# TOP.net
KiCad netlist of a schematic drawn in Altium Designer
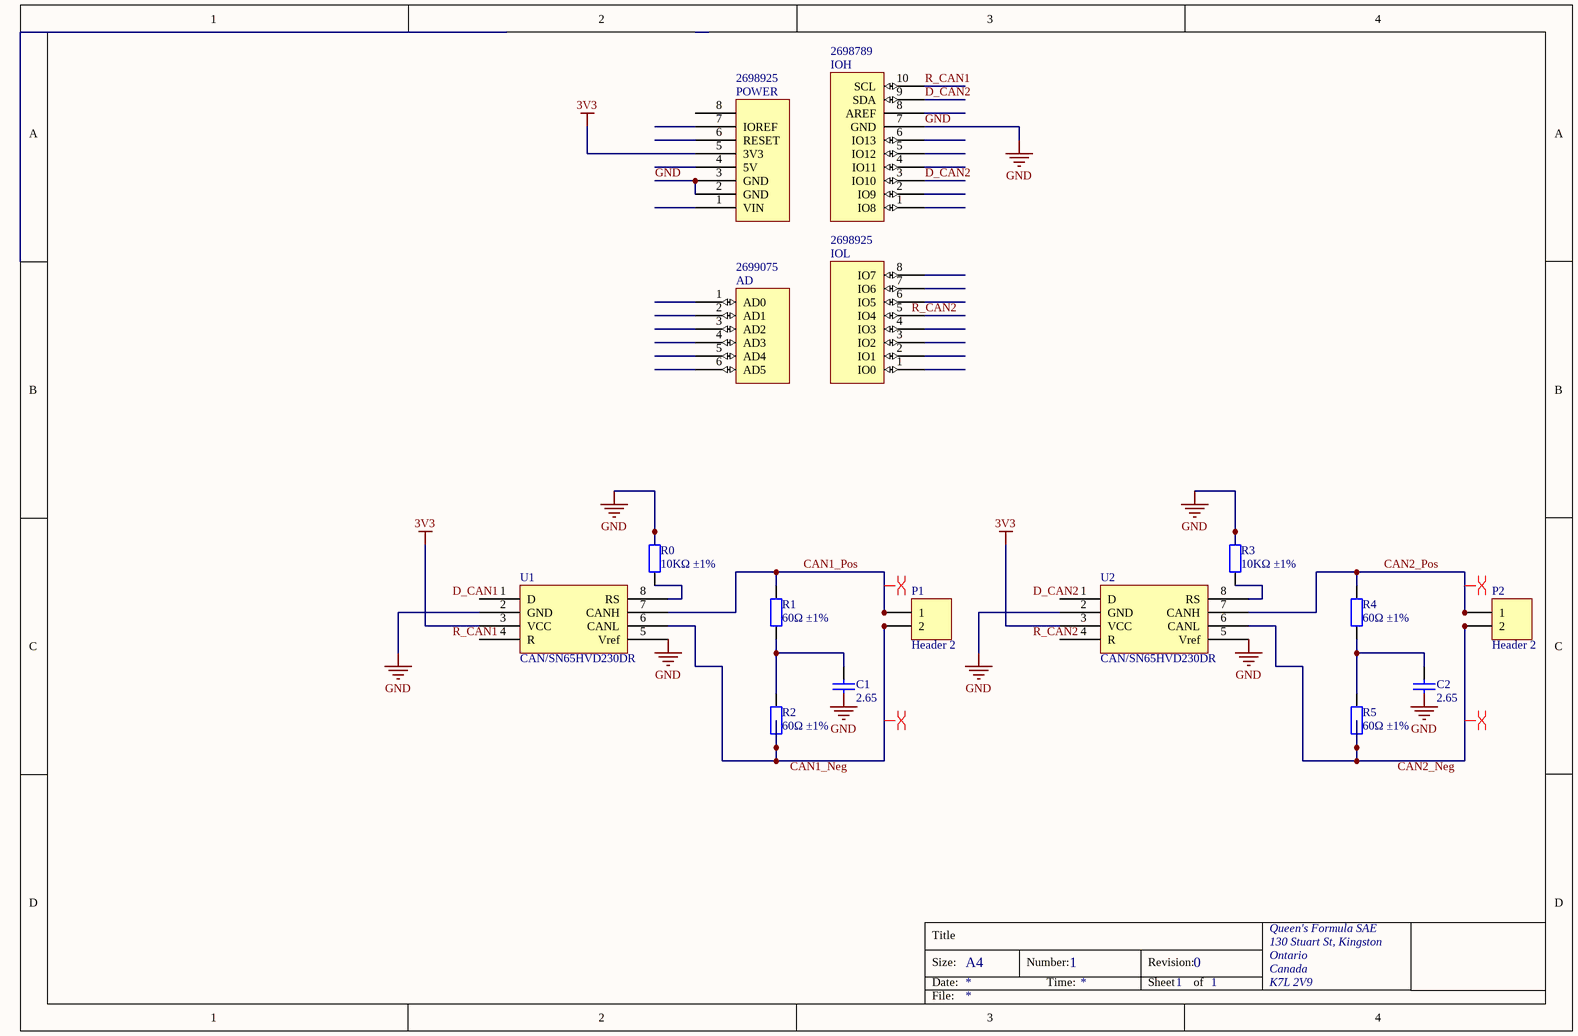
[diagram p0: TOP.SchDoc]

(export (version "E")
  (design (tool "Eeschema 10.0.6"))
  (components
    (comp (ref "AD")
      (value "AD")
      (footprint "Header:Header 6x1 8.5mm")
      (fields (field (name "SUPPLIER PART NUMBER 4") "2699075"))
      (libsource (lib "Header") (part "AD"))
    )
    (comp (ref "C1")
      (value "2.65")
      (footprint "0402_C")
      (description "Chip capacitor")
      (fields
        (field (name "MANUFACTURER") "Guangdong Fenghua Advanced Tech")
        (field (name "PARTNUMBER") "0402B102K500NT")
      )
      (libsource (lib "Cap") (part "0402 1nF (102) 10% 50V"))
    )
    (comp (ref "C2")
      (value "2.65")
      (footprint "0402_C")
      (description "Chip capacitor")
      (fields
        (field (name "MANUFACTURER") "Guangdong Fenghua Advanced Tech")
        (field (name "PARTNUMBER") "0402B102K500NT")
      )
      (libsource (lib "Cap") (part "0402 1nF (102) 10% 50V"))
    )
    (comp (ref "IOH")
      (value "IOH")
      (footprint "Header:Header 10x1 8.5mm")
      (fields (field (name "SUPPLIER PART NUMBER 3") "2698789"))
      (libsource (lib "Header") (part "IOH"))
    )
    (comp (ref "IOL")
      (value "IOL")
      (footprint "Header 8x1 8.5mm")
      (fields (field (name "SUPPLIER PART NUMBER 4") "2698925"))
      (libsource (lib "Header") (part "IOL"))
    )
    (comp (ref "P1")
      (value "Header 2")
      (footprint "HDR1X2")
      (description "Header, 2-Pin")
      (fields (field (name "PUBLISHER") "Altium Limited"))
      (libsource (lib "Miscellaneous Connectors") (part "Header 2"))
    )
    (comp (ref "P2")
      (value "Header 2")
      (footprint "HDR1X2")
      (description "Header, 2-Pin")
      (fields (field (name "PUBLISHER") "Altium Limited"))
      (libsource (lib "Miscellaneous Connectors") (part "Header 2"))
    )
    (comp (ref "POWER")
      (value "POWER_UNO")
      (footprint "Header 8x1 8.5mm")
      (fields (field (name "SUPPLIER PART NUMBER 4") "2698925"))
      (libsource (lib "Header") (part "POWER_UNO"))
    )
    (comp (ref "R0")
      (value "10KΩ ±1%")
      (footprint "0402_R")
      (description "Chip resistor")
      (fields (field (name "MANUFACTURER") "Uniroyal Elec") (field (name "PARTNUMBER") "0402WGF1002TCE"))
      (libsource (lib "RES") (part "0402 10K (1002) 1%"))
    )
    (comp (ref "R1")
      (value "60Ω ±1%")
      (footprint "0402_R")
      (description "Chip resistor")
      (fields (field (name "MANUFACTURER") "Uniroyal Elec") (field (name "PARTNUMBER") "0402WGF1002TCE"))
      (libsource (lib "RES") (part "0402 10K (1002) 1%"))
    )
    (comp (ref "R2")
      (value "60Ω ±1%")
      (footprint "0402_R")
      (description "Chip resistor")
      (fields (field (name "MANUFACTURER") "Uniroyal Elec") (field (name "PARTNUMBER") "0402WGF1002TCE"))
      (libsource (lib "RES") (part "0402 10K (1002) 1%"))
    )
    (comp (ref "R3")
      (value "10KΩ ±1%")
      (footprint "0402_R")
      (description "Chip resistor")
      (fields (field (name "MANUFACTURER") "Uniroyal Elec") (field (name "PARTNUMBER") "0402WGF1002TCE"))
      (libsource (lib "RES") (part "0402 10K (1002) 1%"))
    )
    (comp (ref "R4")
      (value "60Ω ±1%")
      (footprint "0402_R")
      (description "Chip resistor")
      (fields (field (name "MANUFACTURER") "Uniroyal Elec") (field (name "PARTNUMBER") "0402WGF1002TCE"))
      (libsource (lib "RES") (part "0402 10K (1002) 1%"))
    )
    (comp (ref "R5")
      (value "60Ω ±1%")
      (footprint "0402_R")
      (description "Chip resistor")
      (fields (field (name "MANUFACTURER") "Uniroyal Elec") (field (name "PARTNUMBER") "0402WGF1002TCE"))
      (libsource (lib "RES") (part "0402 10K (1002) 1%"))
    )
    (comp (ref "U1")
      (value "CAN/SN65HVD230DR")
      (footprint "SOIC-8_150mil")
      (description "CAN")
      (libsource (lib "IC") (part "CAN/SN65HVD230DR_[C12084]"))
    )
    (comp (ref "U2")
      (value "CAN/SN65HVD230DR")
      (footprint "SOIC-8_150mil")
      (description "CAN")
      (libsource (lib "IC") (part "CAN/SN65HVD230DR_[C12084]"))
    )
  )
  (nets
    (net (code "2") (name "/CAN1_Pos") (class "Default")
      (node (ref "P1") (pin "1") (pinfunction "1_1") (pintype "passive"))
      (node (ref "R1") (pin "2") (pinfunction "2_2") (pintype "passive"))
      (node (ref "U1") (pin "7") (pinfunction "CANH_7") (pintype "passive"))
    )
    (net (code "4") (name "/CAN2_Pos") (class "Default")
      (node (ref "P2") (pin "1") (pinfunction "1_1") (pintype "passive"))
      (node (ref "R4") (pin "2") (pinfunction "2_2") (pintype "passive"))
      (node (ref "U2") (pin "7") (pinfunction "CANH_7") (pintype "passive"))
    )
    (net (code "6") (name "/D_CAN2") (class "Default")
      (node (ref "IOH") (pin "3") (pinfunction "IO10_3") (pintype "bidirectional"))
      (node (ref "IOH") (pin "9") (pinfunction "SDA_9") (pintype "bidirectional"))
    )
    (net (code "7") (name "/R_CAN1") (class "Default")
      (node (ref "IOH") (pin "10") (pinfunction "SCL_10") (pintype "bidirectional"))
    )
    (net (code "9") (name "3V3") (class "Default")
      (node (ref "POWER") (pin "5") (pinfunction "3V3_5") (pintype "power_in"))
      (node (ref "U1") (pin "3") (pinfunction "VCC_3") (pintype "passive"))
      (node (ref "U2") (pin "3") (pinfunction "VCC_3") (pintype "passive"))
    )
    (net (code "10") (name "GND") (class "Default")
      (node (ref "IOH") (pin "7") (pinfunction "GND_7") (pintype "power_in"))
      (node (ref "POWER") (pin "2") (pinfunction "GND_2") (pintype "power_in"))
      (node (ref "POWER") (pin "3") (pinfunction "GND_3") (pintype "power_in"))
      (node (ref "R0") (pin "2") (pinfunction "2_2") (pintype "passive"))
      (node (ref "R3") (pin "2") (pinfunction "2_2") (pintype "passive"))
      (node (ref "U1") (pin "2") (pinfunction "GND_2") (pintype "passive"))
      (node (ref "U1") (pin "5") (pinfunction "Vref_5") (pintype "passive"))
      (node (ref "U2") (pin "2") (pinfunction "GND_2") (pintype "passive"))
      (node (ref "U2") (pin "5") (pinfunction "Vref_5") (pintype "passive"))
    )
    (net (code "11") (name "Net-(C1-Pad1)") (class "Default")
      (node (ref "C1") (pin "1") (pinfunction "1_1") (pintype "passive"))
      (node (ref "R1") (pin "1") (pinfunction "1_1") (pintype "passive"))
      (node (ref "R2") (pin "2") (pinfunction "2_2") (pintype "passive"))
    )
    (net (code "12") (name "Net-(C2-Pad1)") (class "Default")
      (node (ref "C2") (pin "1") (pinfunction "1_1") (pintype "passive"))
      (node (ref "R4") (pin "1") (pinfunction "1_1") (pintype "passive"))
      (node (ref "R5") (pin "2") (pinfunction "2_2") (pintype "passive"))
    )
    (net (code "13") (name "Net-(U1-CANL)") (class "Default")
      (node (ref "P1") (pin "2") (pinfunction "2_2") (pintype "passive"))
      (node (ref "R2") (pin "1") (pinfunction "1_1") (pintype "passive"))
      (node (ref "U1") (pin "6") (pinfunction "CANL_6") (pintype "passive"))
    )
    (net (code "14") (name "Net-(U1-RS)") (class "Default")
      (node (ref "R0") (pin "1") (pinfunction "1_1") (pintype "passive"))
      (node (ref "U1") (pin "8") (pinfunction "RS_8") (pintype "passive"))
    )
    (net (code "15") (name "Net-(U2-CANL)") (class "Default")
      (node (ref "P2") (pin "2") (pinfunction "2_2") (pintype "passive"))
      (node (ref "R5") (pin "1") (pinfunction "1_1") (pintype "passive"))
      (node (ref "U2") (pin "6") (pinfunction "CANL_6") (pintype "passive"))
    )
    (net (code "16") (name "Net-(U2-RS)") (class "Default")
      (node (ref "R3") (pin "1") (pinfunction "1_1") (pintype "passive"))
      (node (ref "U2") (pin "8") (pinfunction "RS_8") (pintype "passive"))
    )
    (net (code "17") (name "unconnected-(AD-AD0-Pad1)") (class "Default")
      (node (ref "AD") (pin "1") (pinfunction "AD0_1") (pintype "bidirectional"))
    )
    (net (code "18") (name "unconnected-(AD-AD1-Pad2)") (class "Default")
      (node (ref "AD") (pin "2") (pinfunction "AD1_2") (pintype "bidirectional"))
    )
    (net (code "19") (name "unconnected-(AD-AD2-Pad3)") (class "Default")
      (node (ref "AD") (pin "3") (pinfunction "AD2_3") (pintype "bidirectional"))
    )
    (net (code "20") (name "unconnected-(AD-AD3-Pad4)") (class "Default")
      (node (ref "AD") (pin "4") (pinfunction "AD3_4") (pintype "bidirectional"))
    )
    (net (code "21") (name "unconnected-(AD-AD4-Pad5)") (class "Default")
      (node (ref "AD") (pin "5") (pinfunction "AD4_5") (pintype "bidirectional"))
    )
    (net (code "22") (name "unconnected-(AD-AD5-Pad6)") (class "Default")
      (node (ref "AD") (pin "6") (pinfunction "AD5_6") (pintype "bidirectional"))
    )
    (net (code "23") (name "unconnected-(C1-Pad2)") (class "Default")
      (node (ref "C1") (pin "2") (pinfunction "2_2") (pintype "passive"))
    )
    (net (code "24") (name "unconnected-(C2-Pad2)") (class "Default")
      (node (ref "C2") (pin "2") (pinfunction "2_2") (pintype "passive"))
    )
    (net (code "25") (name "unconnected-(IOH-AREF-Pad8)") (class "Default")
      (node (ref "IOH") (pin "8") (pinfunction "AREF_8") (pintype "passive"))
    )
    (net (code "26") (name "unconnected-(IOH-IO8-Pad1)") (class "Default")
      (node (ref "IOH") (pin "1") (pinfunction "IO8_1") (pintype "bidirectional"))
    )
    (net (code "27") (name "unconnected-(IOH-IO9-Pad2)") (class "Default")
      (node (ref "IOH") (pin "2") (pinfunction "IO9_2") (pintype "bidirectional"))
    )
    (net (code "28") (name "unconnected-(IOH-IO11-Pad4)") (class "Default")
      (node (ref "IOH") (pin "4") (pinfunction "IO11_4") (pintype "bidirectional"))
    )
    (net (code "29") (name "unconnected-(IOH-IO12-Pad5)") (class "Default")
      (node (ref "IOH") (pin "5") (pinfunction "IO12_5") (pintype "bidirectional"))
    )
    (net (code "30") (name "unconnected-(IOH-IO13-Pad6)") (class "Default")
      (node (ref "IOH") (pin "6") (pinfunction "IO13_6") (pintype "bidirectional"))
    )
    (net (code "31") (name "unconnected-(IOL-IO0-Pad1)") (class "Default")
      (node (ref "IOL") (pin "1") (pinfunction "IO0_1") (pintype "bidirectional"))
    )
    (net (code "32") (name "unconnected-(IOL-IO1-Pad2)") (class "Default")
      (node (ref "IOL") (pin "2") (pinfunction "IO1_2") (pintype "bidirectional"))
    )
    (net (code "33") (name "unconnected-(IOL-IO2-Pad3)") (class "Default")
      (node (ref "IOL") (pin "3") (pinfunction "IO2_3") (pintype "bidirectional"))
    )
    (net (code "34") (name "unconnected-(IOL-IO3-Pad4)") (class "Default")
      (node (ref "IOL") (pin "4") (pinfunction "IO3_4") (pintype "bidirectional"))
    )
    (net (code "35") (name "unconnected-(IOL-IO4-Pad5)") (class "Default")
      (node (ref "IOL") (pin "5") (pinfunction "IO4_5") (pintype "bidirectional"))
    )
    (net (code "36") (name "unconnected-(IOL-IO5-Pad6)") (class "Default")
      (node (ref "IOL") (pin "6") (pinfunction "IO5_6") (pintype "bidirectional"))
    )
    (net (code "37") (name "unconnected-(IOL-IO6-Pad7)") (class "Default")
      (node (ref "IOL") (pin "7") (pinfunction "IO6_7") (pintype "bidirectional"))
    )
    (net (code "38") (name "unconnected-(IOL-IO7-Pad8)") (class "Default")
      (node (ref "IOL") (pin "8") (pinfunction "IO7_8") (pintype "bidirectional"))
    )
    (net (code "39") (name "unconnected-(POWER-5V-Pad4)") (class "Default")
      (node (ref "POWER") (pin "4") (pinfunction "5V_4") (pintype "power_in"))
    )
    (net (code "40") (name "unconnected-(POWER-IOREF-Pad7)") (class "Default")
      (node (ref "POWER") (pin "7") (pinfunction "IOREF_7") (pintype "power_in"))
    )
    (net (code "41") (name "unconnected-(POWER-Pad8)") (class "Default")
      (node (ref "POWER") (pin "8") (pintype "passive"))
    )
    (net (code "42") (name "unconnected-(POWER-RESET-Pad6)") (class "Default")
      (node (ref "POWER") (pin "6") (pinfunction "RESET_6") (pintype "passive"))
    )
    (net (code "43") (name "unconnected-(POWER-VIN-Pad1)") (class "Default")
      (node (ref "POWER") (pin "1") (pinfunction "VIN_1") (pintype "power_in"))
    )
    (net (code "44") (name "unconnected-(U1-D-Pad1)") (class "Default")
      (node (ref "U1") (pin "1") (pinfunction "D_1") (pintype "passive"))
    )
    (net (code "45") (name "unconnected-(U1-R-Pad4)") (class "Default")
      (node (ref "U1") (pin "4") (pinfunction "R_4") (pintype "passive"))
    )
    (net (code "46") (name "unconnected-(U2-D-Pad1)") (class "Default")
      (node (ref "U2") (pin "1") (pinfunction "D_1") (pintype "passive"))
    )
    (net (code "47") (name "unconnected-(U2-R-Pad4)") (class "Default")
      (node (ref "U2") (pin "4") (pinfunction "R_4") (pintype "passive"))
    )
  )
)
